# Solenoid_Boardv2.net
KiCad netlist of a schematic drawn in EAGLE
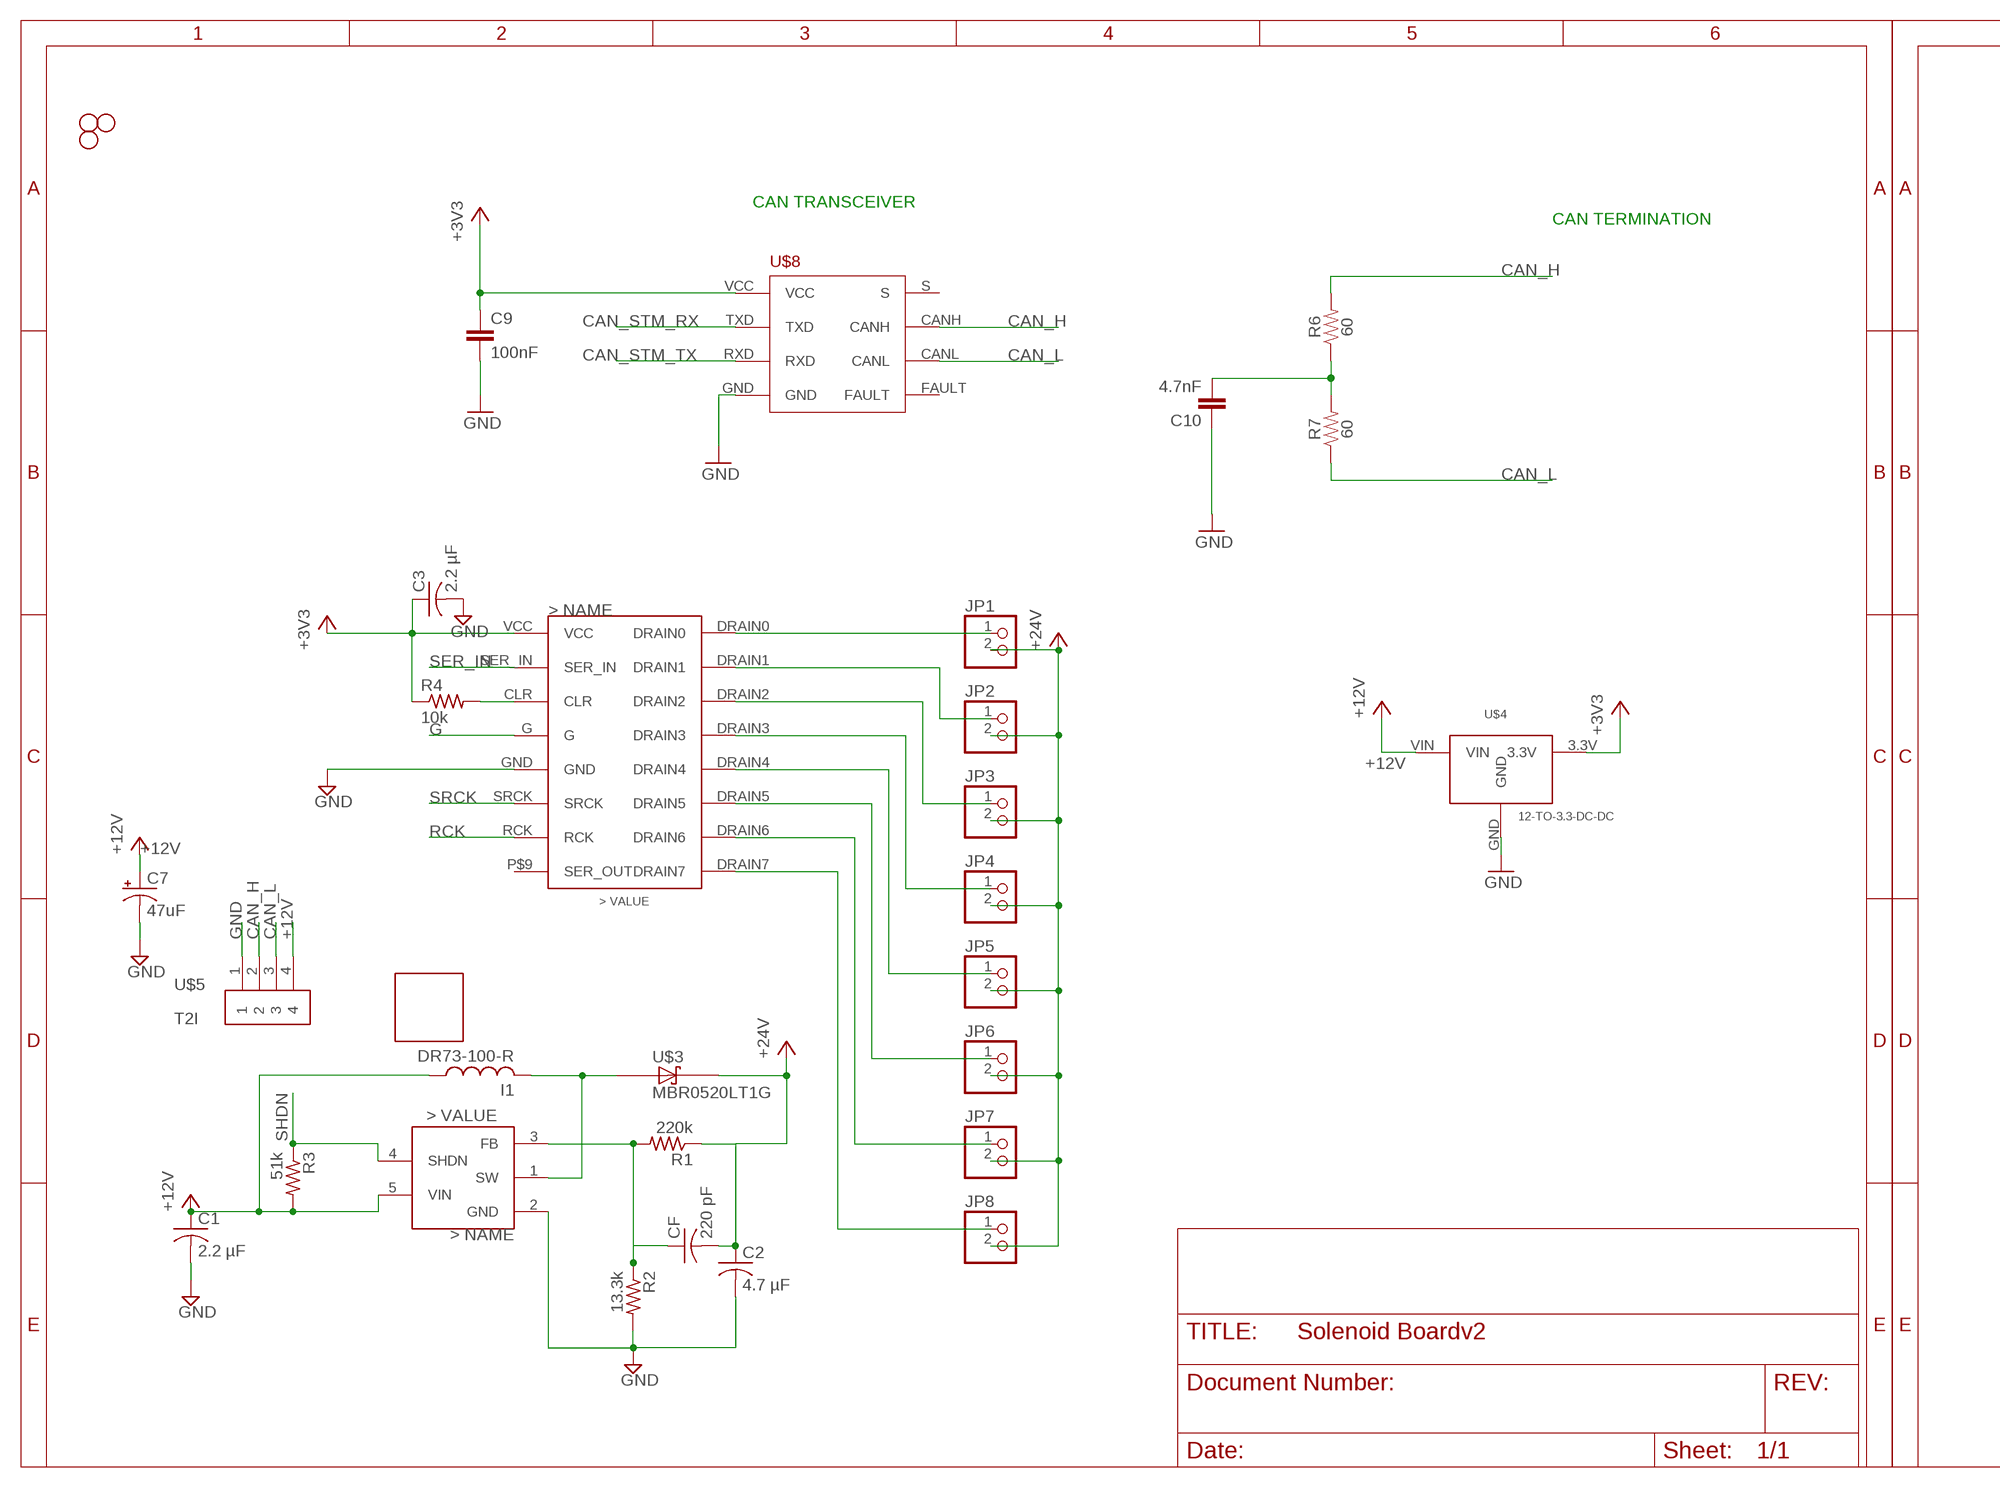
[diagram p0: schematic, sheet 1, part 1 of 2]
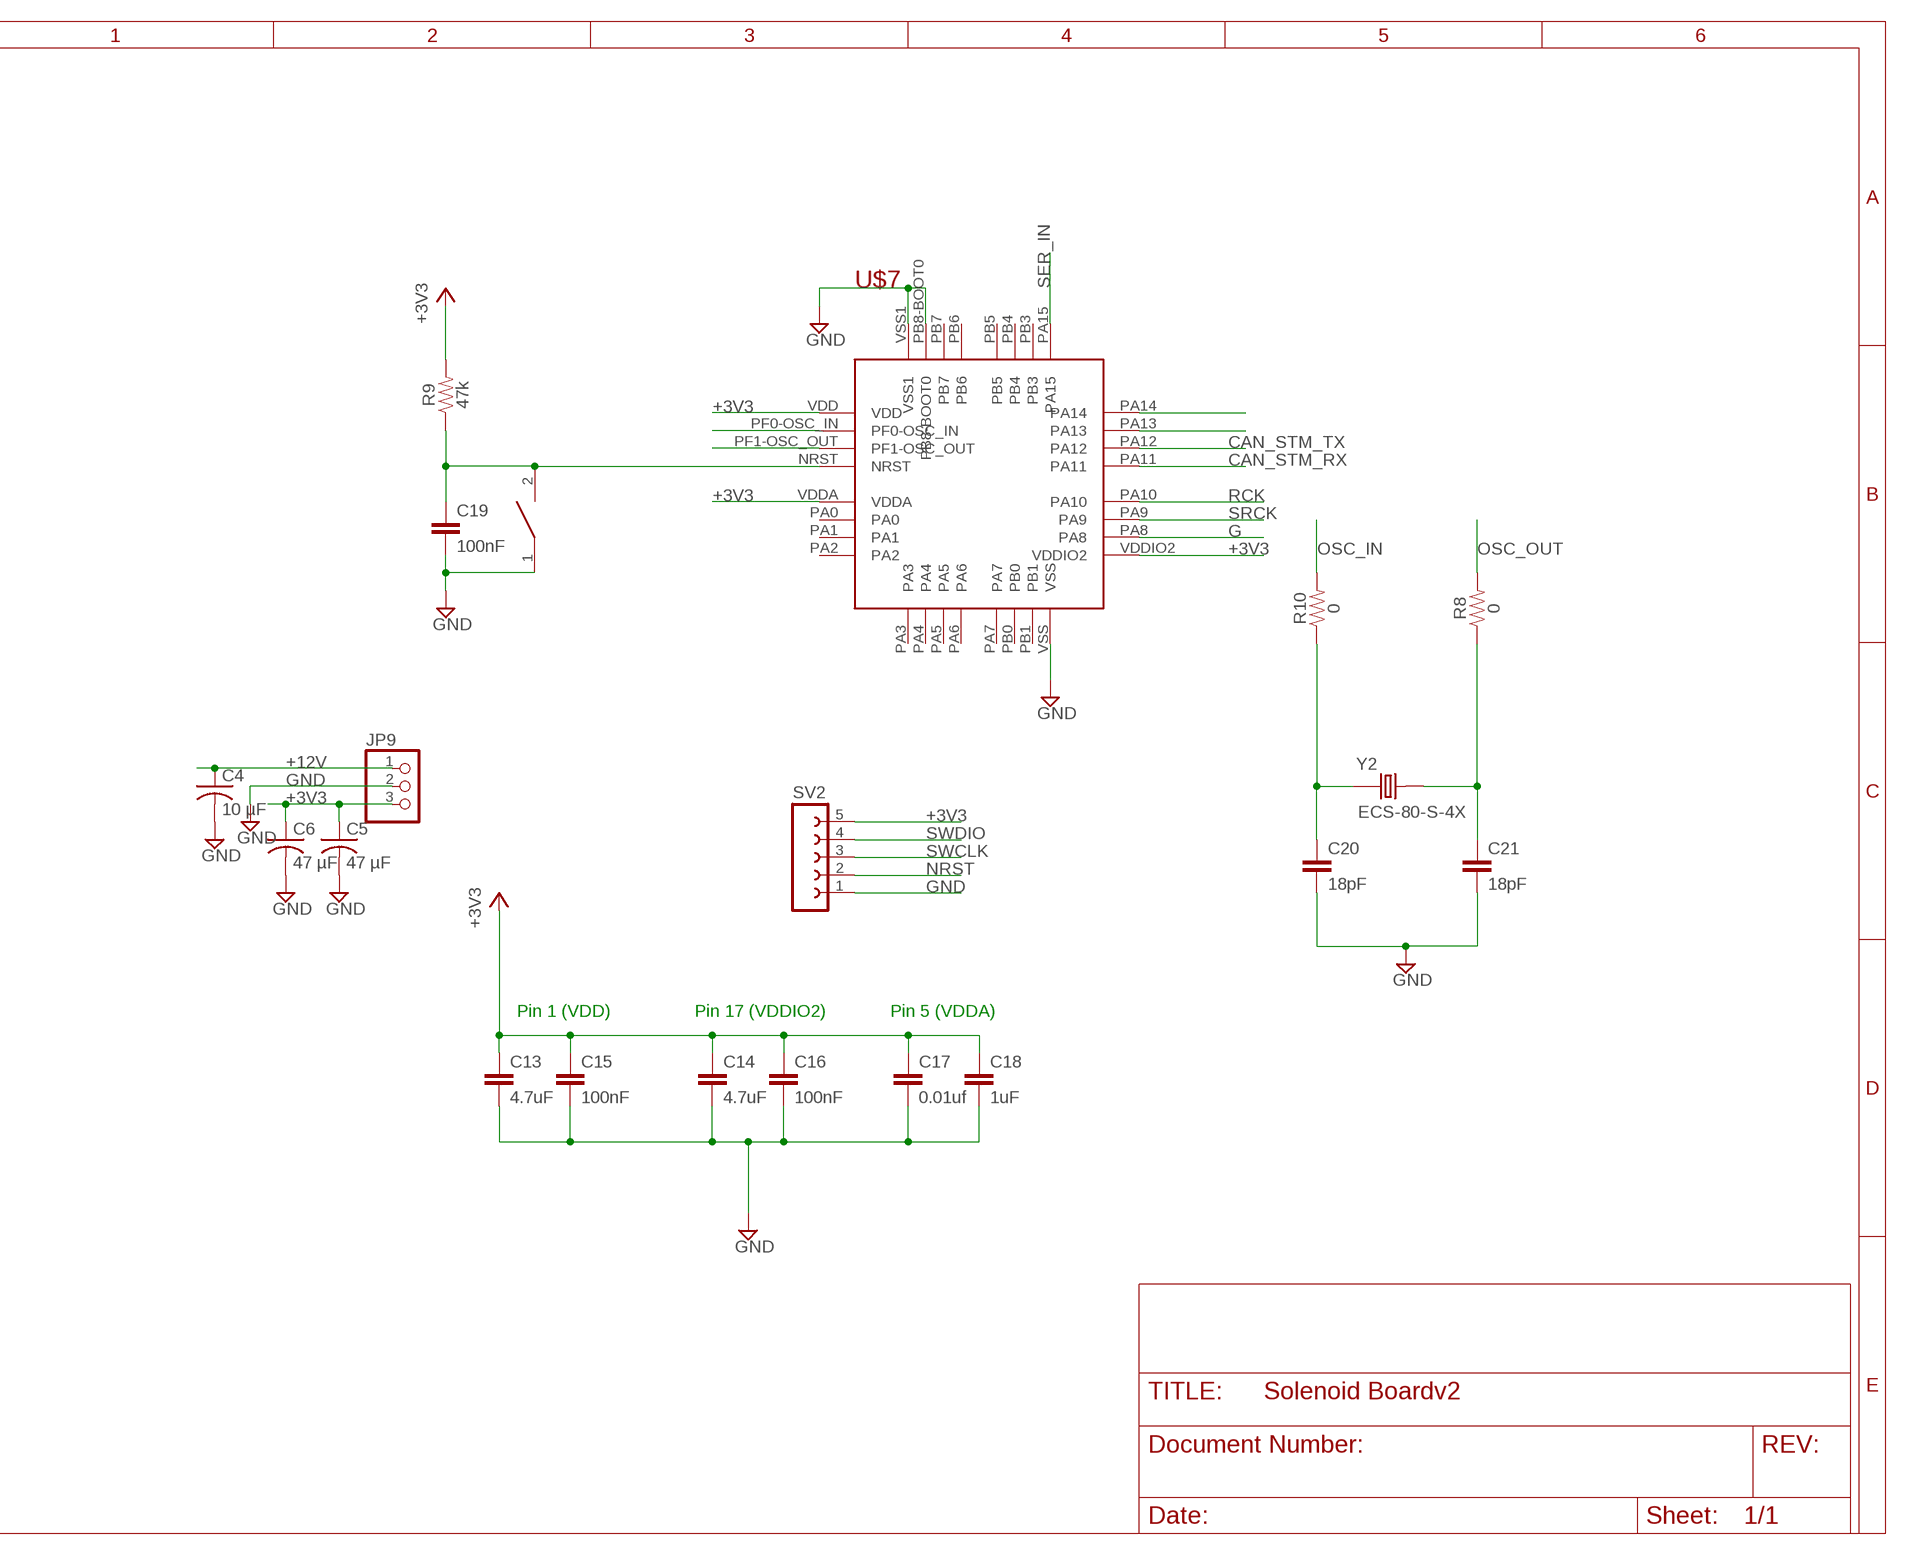
[diagram p1: schematic, sheet 1, part 2 of 2]

(export (version "E")
  (design (tool "Eeschema 10.0.6"))
  (components
    (comp (ref "C1")
      (value "2.2 µF")
      (footprint "eagle-import:C0805")
      (libsource (lib "eagle-import") (part "C-USC0805"))
    )
    (comp (ref "C2")
      (value "4.7 µF")
      (footprint "eagle-import:C0805")
      (libsource (lib "eagle-import") (part "C-USC0805"))
    )
    (comp (ref "C3")
      (value "2.2 µF")
      (footprint "eagle-import:C0805")
      (libsource (lib "eagle-import") (part "C-USC0805"))
    )
    (comp (ref "C4")
      (value "10 µF")
      (footprint "eagle-import:C0805")
      (libsource (lib "eagle-import") (part "C-USC0805"))
    )
    (comp (ref "C5")
      (value "47 µF")
      (footprint "eagle-import:C0805")
      (libsource (lib "eagle-import") (part "C-USC0805"))
    )
    (comp (ref "C6")
      (value "47 µF")
      (footprint "eagle-import:C0805")
      (libsource (lib "eagle-import") (part "C-USC0805"))
    )
    (comp (ref "C7")
      (value "47uF")
      (footprint "eagle-import:PANASONIC_D")
      (libsource (lib "eagle-import") (part "47UF-POLAR-PANASONIC_D-35V-20%"))
    )
    (comp (ref "C9")
      (value "100nF")
      (footprint "eagle-import:0603")
      (libsource (lib "eagle-import") (part "4.7UF0603"))
    )
    (comp (ref "C10")
      (value "4.7nF")
      (footprint "eagle-import:0603")
      (libsource (lib "eagle-import") (part "0.1UF-0603-25V-(+80/-20%)"))
    )
    (comp (ref "C13")
      (value "4.7uF")
      (footprint "eagle-import:0603")
      (libsource (lib "eagle-import") (part "4.7UF0603"))
    )
    (comp (ref "C14")
      (value "4.7uF")
      (footprint "eagle-import:0603")
      (libsource (lib "eagle-import") (part "4.7UF0603"))
    )
    (comp (ref "C15")
      (value "100nF")
      (footprint "eagle-import:0603")
      (libsource (lib "eagle-import") (part "4.7UF0603"))
    )
    (comp (ref "C16")
      (value "100nF")
      (footprint "eagle-import:0603")
      (libsource (lib "eagle-import") (part "4.7UF0603"))
    )
    (comp (ref "C17")
      (value "0.01uf")
      (footprint "eagle-import:0603")
      (libsource (lib "eagle-import") (part "4.7UF0603"))
    )
    (comp (ref "C18")
      (value "1uF")
      (footprint "eagle-import:0603")
      (libsource (lib "eagle-import") (part "4.7UF0603"))
    )
    (comp (ref "C19")
      (value "100nF")
      (footprint "eagle-import:0603")
      (libsource (lib "eagle-import") (part "4.7UF0603"))
    )
    (comp (ref "C20")
      (value "18pF")
      (footprint "eagle-import:0603")
      (libsource (lib "eagle-import") (part "4.7UF0603"))
    )
    (comp (ref "C21")
      (value "18pF")
      (footprint "eagle-import:0603")
      (libsource (lib "eagle-import") (part "4.7UF0603"))
    )
    (comp (ref "CF")
      (value "220 pF")
      (footprint "eagle-import:C0805")
      (libsource (lib "eagle-import") (part "C-USC0805"))
    )
    (comp (ref "H1")
      (value "STAND-OFF")
      (footprint "eagle-import:STAND-OFF")
      (libsource (lib "eagle-import") (part "STAND-OFF"))
    )
    (comp (ref "H2")
      (value "STAND-OFF")
      (footprint "eagle-import:STAND-OFF")
      (libsource (lib "eagle-import") (part "STAND-OFF"))
    )
    (comp (ref "H3")
      (value "STAND-OFF")
      (footprint "eagle-import:STAND-OFF")
      (libsource (lib "eagle-import") (part "STAND-OFF"))
    )
    (comp (ref "I1")
      (value "DR73-100-R")
      (footprint "eagle-import:DR73-100-R")
      (libsource (lib "eagle-import") (part "DR73-100-R"))
    )
    (comp (ref "JP1")
      (value "PINHD-1X2")
      (footprint "eagle-import:1X02")
      (libsource (lib "eagle-import") (part "PINHD-1X2"))
    )
    (comp (ref "JP2")
      (value "PINHD-1X2")
      (footprint "eagle-import:1X02")
      (libsource (lib "eagle-import") (part "PINHD-1X2"))
    )
    (comp (ref "JP3")
      (value "PINHD-1X2")
      (footprint "eagle-import:1X02")
      (libsource (lib "eagle-import") (part "PINHD-1X2"))
    )
    (comp (ref "JP4")
      (value "PINHD-1X2")
      (footprint "eagle-import:1X02")
      (libsource (lib "eagle-import") (part "PINHD-1X2"))
    )
    (comp (ref "JP5")
      (value "PINHD-1X2")
      (footprint "eagle-import:1X02")
      (libsource (lib "eagle-import") (part "PINHD-1X2"))
    )
    (comp (ref "JP6")
      (value "PINHD-1X2")
      (footprint "eagle-import:1X02")
      (libsource (lib "eagle-import") (part "PINHD-1X2"))
    )
    (comp (ref "JP7")
      (value "PINHD-1X2")
      (footprint "eagle-import:1X02")
      (libsource (lib "eagle-import") (part "PINHD-1X2"))
    )
    (comp (ref "JP8")
      (value "PINHD-1X2")
      (footprint "eagle-import:1X02")
      (libsource (lib "eagle-import") (part "PINHD-1X2"))
    )
    (comp (ref "JP9")
      (value "PINHD-1X3")
      (footprint "eagle-import:1X03")
      (libsource (lib "eagle-import") (part "PINHD-1X3"))
    )
    (comp (ref "R1")
      (value "220k")
      (footprint "eagle-import:R0603")
      (libsource (lib "eagle-import") (part "R-US_R0603"))
    )
    (comp (ref "R2")
      (value "13.3k")
      (footprint "eagle-import:R0603")
      (libsource (lib "eagle-import") (part "R-US_R0603"))
    )
    (comp (ref "R3")
      (value "51k")
      (footprint "eagle-import:R0603")
      (libsource (lib "eagle-import") (part "R-US_R0603"))
    )
    (comp (ref "R4")
      (value "10k")
      (footprint "eagle-import:R0603")
      (libsource (lib "eagle-import") (part "R-US_R0603"))
    )
    (comp (ref "R6")
      (value "60")
      (footprint "eagle-import:0603")
      (libsource (lib "eagle-import") (part "1KOHM-0603-1/10W-1%"))
    )
    (comp (ref "R7")
      (value "60")
      (footprint "eagle-import:0603")
      (libsource (lib "eagle-import") (part "1KOHM-0603-1/10W-1%"))
    )
    (comp (ref "R8")
      (value "0")
      (footprint "eagle-import:0603")
      (libsource (lib "eagle-import") (part "1KOHM-0603-1/10W-1%"))
    )
    (comp (ref "R9")
      (value "47k")
      (footprint "eagle-import:0603")
      (libsource (lib "eagle-import") (part "1KOHM-0603-1/10W-1%"))
    )
    (comp (ref "R10")
      (value "0")
      (footprint "eagle-import:0603")
      (libsource (lib "eagle-import") (part "1KOHM-0603-1/10W-1%"))
    )
    (comp (ref "RESET1")
      (value "SWITCH")
      (footprint "eagle-import:SW_2512")
      (libsource (lib "eagle-import") (part "SWITCH"))
    )
    (comp (ref "SV2")
      (value "FE05-1")
      (footprint "eagle-import:FE05-1")
      (libsource (lib "eagle-import") (part "FE05-1"))
    )
    (comp (ref "U$1")
      (value "SHIFT_REGISTER")
      (footprint "eagle-import:SHIFT_REGISTER")
      (libsource (lib "eagle-import") (part "SHIFT_REGISTER"))
    )
    (comp (ref "U$2")
      (value "LM27313")
      (footprint "eagle-import:SOT95P300X145-5")
      (libsource (lib "eagle-import") (part "LM27313"))
    )
    (comp (ref "U$3")
      (value "MBR0520LT1G")
      (footprint "eagle-import:SOD3716X135")
      (libsource (lib "eagle-import") (part "MBR0520LT1G"))
    )
    (comp (ref "U$4")
      (value "12-TO-3.3-DC-DC")
      (footprint "eagle-import:MURATA-DCDC")
      (libsource (lib "eagle-import") (part "12-TO-3.3-DC-DC"))
    )
    (comp (ref "U$5")
      (value "T2I")
      (footprint "eagle-import:T2I")
      (libsource (lib "eagle-import") (part "T2I"))
    )
    (comp (ref "U$6")
      (value "BOARDPNE")
      (footprint "eagle-import:PNE")
      (libsource (lib "eagle-import") (part "BOARDPNE"))
    )
    (comp (ref "U$7")
      (value "STM32F042K6T6")
      (footprint "eagle-import:STM32F042K6T6")
      (libsource (lib "eagle-import") (part "STM32F042K6T6"))
    )
    (comp (ref "U$8")
      (value "TCAN337D")
      (footprint "eagle-import:TCAN337D")
      (libsource (lib "eagle-import") (part "TCAN337D"))
    )
    (comp (ref "Y2")
      (value "ECS-80-S-4X")
      (footprint "eagle-import:XTAL_ECS-80-S-4X")
      (fields (field (name "DIGI-KEY_PART_NUMBER") "X1057-ND") (field (name "MF") "ECS International"))
      (libsource (lib "eagle-import") (part "ECS-80-S-4X"))
    )
  )
  (nets
    (net (code "1") (name "+3V3") (class "Default")
      (node (ref "C13") (pin "1") (pinfunction "1_1") (pintype "passive"))
      (node (ref "C14") (pin "1") (pinfunction "1_1") (pintype "passive"))
      (node (ref "C15") (pin "1") (pinfunction "1_1") (pintype "passive"))
      (node (ref "C16") (pin "1") (pinfunction "1_1") (pintype "passive"))
      (node (ref "C17") (pin "1") (pinfunction "1_1") (pintype "passive"))
      (node (ref "C18") (pin "1") (pinfunction "1_1") (pintype "passive"))
      (node (ref "C3") (pin "1") (pinfunction "1_1") (pintype "passive"))
      (node (ref "C5") (pin "1") (pinfunction "1_1") (pintype "passive"))
      (node (ref "C6") (pin "1") (pinfunction "1_1") (pintype "passive"))
      (node (ref "C9") (pin "1") (pinfunction "1_1") (pintype "passive"))
      (node (ref "JP9") (pin "3") (pinfunction "3_3") (pintype "passive"))
      (node (ref "R4") (pin "1") (pinfunction "1_1") (pintype "passive"))
      (node (ref "R9") (pin "2") (pinfunction "2_2") (pintype "passive"))
      (node (ref "SV2") (pin "5") (pinfunction "5_5") (pintype "passive"))
      (node (ref "U$1") (pin "VCC") (pinfunction "VCC_VCC") (pintype "bidirectional"))
      (node (ref "U$4") (pin "3.3V") (pinfunction "3.3V_3.3V") (pintype "bidirectional"))
      (node (ref "U$7") (pin "VDD") (pinfunction "VDD_VDD") (pintype "bidirectional"))
      (node (ref "U$7") (pin "VDDA") (pinfunction "VDDA_VDDA") (pintype "bidirectional"))
      (node (ref "U$7") (pin "VDDIO2") (pinfunction "VDDIO2_VDDIO2") (pintype "bidirectional"))
      (node (ref "U$8") (pin "VCC") (pinfunction "VCC_VCC") (pintype "bidirectional"))
    )
    (net (code "2") (name "+12V") (class "Default")
      (node (ref "C1") (pin "1") (pinfunction "1_1") (pintype "passive"))
      (node (ref "C4") (pin "1") (pinfunction "1_1") (pintype "passive"))
      (node (ref "C7") (pin "+") (pinfunction "+_+") (pintype "passive"))
      (node (ref "I1") (pin "1") (pinfunction "1_1") (pintype "passive"))
      (node (ref "JP9") (pin "1") (pinfunction "1_1") (pintype "passive"))
      (node (ref "R3") (pin "2") (pinfunction "2_2") (pintype "passive"))
      (node (ref "U$2") (pin "5") (pinfunction "VIN_5") (pintype "bidirectional"))
      (node (ref "U$4") (pin "VIN") (pinfunction "VIN_VIN") (pintype "bidirectional"))
      (node (ref "U$5") (pin "4") (pinfunction "4_4") (pintype "bidirectional"))
    )
    (net (code "3") (name "+24V") (class "Default")
      (node (ref "C2") (pin "1") (pinfunction "1_1") (pintype "passive"))
      (node (ref "CF") (pin "2") (pinfunction "2_2") (pintype "passive"))
      (node (ref "JP1") (pin "2") (pinfunction "2_2") (pintype "passive"))
      (node (ref "JP2") (pin "2") (pinfunction "2_2") (pintype "passive"))
      (node (ref "JP3") (pin "2") (pinfunction "2_2") (pintype "passive"))
      (node (ref "JP4") (pin "2") (pinfunction "2_2") (pintype "passive"))
      (node (ref "JP5") (pin "2") (pinfunction "2_2") (pintype "passive"))
      (node (ref "JP6") (pin "2") (pinfunction "2_2") (pintype "passive"))
      (node (ref "JP7") (pin "2") (pinfunction "2_2") (pintype "passive"))
      (node (ref "JP8") (pin "2") (pinfunction "2_2") (pintype "passive"))
      (node (ref "R1") (pin "1") (pinfunction "1_1") (pintype "passive"))
      (node (ref "U$3") (pin "2") (pinfunction "C_2") (pintype "passive"))
    )
    (net (code "4") (name "/CAN_H") (class "Default")
      (node (ref "R6") (pin "2") (pinfunction "2_2") (pintype "passive"))
      (node (ref "U$5") (pin "2") (pinfunction "2_2") (pintype "bidirectional"))
      (node (ref "U$8") (pin "CANH") (pinfunction "CANH_CANH") (pintype "bidirectional"))
    )
    (net (code "5") (name "/CAN_L") (class "Default")
      (node (ref "R7") (pin "1") (pinfunction "1_1") (pintype "passive"))
      (node (ref "U$5") (pin "3") (pinfunction "3_3") (pintype "bidirectional"))
      (node (ref "U$8") (pin "CANL") (pinfunction "CANL_CANL") (pintype "bidirectional"))
    )
    (net (code "6") (name "/CAN_STM_RX") (class "Default")
      (node (ref "U$7") (pin "PA11") (pinfunction "PA11_PA11") (pintype "bidirectional"))
      (node (ref "U$8") (pin "TXD") (pinfunction "TXD_TXD") (pintype "bidirectional"))
    )
    (net (code "7") (name "/CAN_STM_TX") (class "Default")
      (node (ref "U$7") (pin "PA12") (pinfunction "PA12_PA12") (pintype "bidirectional"))
      (node (ref "U$8") (pin "RXD") (pinfunction "RXD_RXD") (pintype "bidirectional"))
    )
    (net (code "8") (name "/G") (class "Default")
      (node (ref "U$1") (pin "G") (pinfunction "G_G") (pintype "bidirectional"))
      (node (ref "U$7") (pin "PA8") (pinfunction "PA8_PA8") (pintype "bidirectional"))
    )
    (net (code "9") (name "/NRST") (class "Default")
      (node (ref "C19") (pin "1") (pinfunction "1_1") (pintype "passive"))
      (node (ref "R9") (pin "1") (pinfunction "1_1") (pintype "passive"))
      (node (ref "RESET1") (pin "2") (pinfunction "P$2_2") (pintype "bidirectional"))
      (node (ref "SV2") (pin "2") (pinfunction "2_2") (pintype "passive"))
      (node (ref "U$7") (pin "NRST") (pinfunction "NRST_NRST") (pintype "bidirectional"))
    )
    (net (code "10") (name "/OSC_IN") (class "Default")
      (node (ref "R10") (pin "2") (pinfunction "2_2") (pintype "passive"))
      (node (ref "U$7") (pin "PF0-OSC_IN") (pinfunction "PF0-OSC_IN_PF0-OSC_IN") (pintype "bidirectional"))
    )
    (net (code "11") (name "/OSC_OUT") (class "Default")
      (node (ref "R8") (pin "2") (pinfunction "2_2") (pintype "passive"))
      (node (ref "U$7") (pin "PF1-OSC_OUT") (pinfunction "PF1-OSC_OUT_PF1-OSC_OUT") (pintype "bidirectional"))
    )
    (net (code "12") (name "/RCK") (class "Default")
      (node (ref "U$1") (pin "RCK") (pinfunction "RCK_RCK") (pintype "bidirectional"))
      (node (ref "U$7") (pin "PA10") (pinfunction "PA10_PA10") (pintype "bidirectional"))
    )
    (net (code "13") (name "/SER_IN") (class "Default")
      (node (ref "U$1") (pin "SER_IN") (pinfunction "SER_IN_SER_IN") (pintype "bidirectional"))
      (node (ref "U$7") (pin "PA15") (pinfunction "PA15_PA15") (pintype "bidirectional"))
    )
    (net (code "14") (name "/SHDN") (class "Default")
      (node (ref "R3") (pin "1") (pinfunction "1_1") (pintype "passive"))
      (node (ref "U$2") (pin "4") (pinfunction "SHDN_4") (pintype "bidirectional"))
    )
    (net (code "15") (name "/SRCK") (class "Default")
      (node (ref "U$1") (pin "SRCK") (pinfunction "SRCK_SRCK") (pintype "bidirectional"))
      (node (ref "U$7") (pin "PA9") (pinfunction "PA9_PA9") (pintype "bidirectional"))
    )
    (net (code "16") (name "/SWCLK") (class "Default")
      (node (ref "SV2") (pin "3") (pinfunction "3_3") (pintype "passive"))
      (node (ref "U$7") (pin "PA14") (pinfunction "PA14_PA14") (pintype "bidirectional"))
    )
    (net (code "17") (name "/SWDIO") (class "Default")
      (node (ref "SV2") (pin "4") (pinfunction "4_4") (pintype "passive"))
      (node (ref "U$7") (pin "PA13") (pinfunction "PA13_PA13") (pintype "bidirectional"))
    )
    (net (code "18") (name "GND") (class "Default")
      (node (ref "C1") (pin "2") (pinfunction "2_2") (pintype "passive"))
      (node (ref "C10") (pin "1") (pinfunction "1_1") (pintype "passive"))
      (node (ref "C13") (pin "2") (pinfunction "2_2") (pintype "passive"))
      (node (ref "C14") (pin "2") (pinfunction "2_2") (pintype "passive"))
      (node (ref "C15") (pin "2") (pinfunction "2_2") (pintype "passive"))
      (node (ref "C16") (pin "2") (pinfunction "2_2") (pintype "passive"))
      (node (ref "C17") (pin "2") (pinfunction "2_2") (pintype "passive"))
      (node (ref "C18") (pin "2") (pinfunction "2_2") (pintype "passive"))
      (node (ref "C19") (pin "2") (pinfunction "2_2") (pintype "passive"))
      (node (ref "C2") (pin "2") (pinfunction "2_2") (pintype "passive"))
      (node (ref "C20") (pin "2") (pinfunction "2_2") (pintype "passive"))
      (node (ref "C21") (pin "2") (pinfunction "2_2") (pintype "passive"))
      (node (ref "C3") (pin "2") (pinfunction "2_2") (pintype "passive"))
      (node (ref "C4") (pin "2") (pinfunction "2_2") (pintype "passive"))
      (node (ref "C5") (pin "2") (pinfunction "2_2") (pintype "passive"))
      (node (ref "C6") (pin "2") (pinfunction "2_2") (pintype "passive"))
      (node (ref "C7") (pin "-") (pinfunction "-_-") (pintype "passive"))
      (node (ref "C9") (pin "2") (pinfunction "2_2") (pintype "passive"))
      (node (ref "JP9") (pin "2") (pinfunction "2_2") (pintype "passive"))
      (node (ref "R2") (pin "2") (pinfunction "2_2") (pintype "passive"))
      (node (ref "RESET1") (pin "1") (pinfunction "P$1_1") (pintype "bidirectional"))
      (node (ref "SV2") (pin "1") (pinfunction "1_1") (pintype "passive"))
      (node (ref "U$1") (pin "GND") (pinfunction "GND_GND") (pintype "bidirectional"))
      (node (ref "U$2") (pin "2") (pinfunction "GND_2") (pintype "bidirectional"))
      (node (ref "U$4") (pin "GND") (pinfunction "GND_GND") (pintype "bidirectional"))
      (node (ref "U$5") (pin "1") (pinfunction "1_1") (pintype "bidirectional"))
      (node (ref "U$7") (pin "PB8-BOOT0") (pinfunction "PB8-BOOT0_PB8-BOOT0") (pintype "bidirectional"))
      (node (ref "U$7") (pin "VSS") (pinfunction "VSS_VSS") (pintype "bidirectional"))
      (node (ref "U$7") (pin "VSS1") (pinfunction "VSS1_VSS1") (pintype "bidirectional"))
      (node (ref "U$8") (pin "GND") (pinfunction "GND_GND") (pintype "bidirectional"))
    )
    (net (code "19") (name "Net-(C10-Pad2)") (class "Default")
      (node (ref "C10") (pin "2") (pinfunction "2_2") (pintype "passive"))
      (node (ref "R6") (pin "1") (pinfunction "1_1") (pintype "passive"))
      (node (ref "R7") (pin "2") (pinfunction "2_2") (pintype "passive"))
    )
    (net (code "20") (name "Net-(C20-Pad1)") (class "Default")
      (node (ref "C20") (pin "1") (pinfunction "1_1") (pintype "passive"))
      (node (ref "R10") (pin "1") (pinfunction "1_1") (pintype "passive"))
      (node (ref "Y2") (pin "1") (pinfunction "1_1") (pintype "passive"))
    )
    (net (code "21") (name "Net-(C21-Pad1)") (class "Default")
      (node (ref "C21") (pin "1") (pinfunction "1_1") (pintype "passive"))
      (node (ref "R8") (pin "1") (pinfunction "1_1") (pintype "passive"))
      (node (ref "Y2") (pin "2") (pinfunction "2_2") (pintype "passive"))
    )
    (net (code "22") (name "Net-(JP1-Pad1)") (class "Default")
      (node (ref "JP1") (pin "1") (pinfunction "1_1") (pintype "passive"))
      (node (ref "U$1") (pin "DRAIN0") (pinfunction "DRAIN0_DRAIN0") (pintype "bidirectional"))
    )
    (net (code "23") (name "Net-(JP2-Pad1)") (class "Default")
      (node (ref "JP2") (pin "1") (pinfunction "1_1") (pintype "passive"))
      (node (ref "U$1") (pin "DRAIN1") (pinfunction "DRAIN1_DRAIN1") (pintype "bidirectional"))
    )
    (net (code "24") (name "Net-(JP3-Pad1)") (class "Default")
      (node (ref "JP3") (pin "1") (pinfunction "1_1") (pintype "passive"))
      (node (ref "U$1") (pin "DRAIN2") (pinfunction "DRAIN2_DRAIN2") (pintype "bidirectional"))
    )
    (net (code "25") (name "Net-(JP4-Pad1)") (class "Default")
      (node (ref "JP4") (pin "1") (pinfunction "1_1") (pintype "passive"))
      (node (ref "U$1") (pin "DRAIN3") (pinfunction "DRAIN3_DRAIN3") (pintype "bidirectional"))
    )
    (net (code "26") (name "Net-(JP5-Pad1)") (class "Default")
      (node (ref "JP5") (pin "1") (pinfunction "1_1") (pintype "passive"))
      (node (ref "U$1") (pin "DRAIN4") (pinfunction "DRAIN4_DRAIN4") (pintype "bidirectional"))
    )
    (net (code "27") (name "Net-(JP6-Pad1)") (class "Default")
      (node (ref "JP6") (pin "1") (pinfunction "1_1") (pintype "passive"))
      (node (ref "U$1") (pin "DRAIN5") (pinfunction "DRAIN5_DRAIN5") (pintype "bidirectional"))
    )
    (net (code "28") (name "Net-(JP7-Pad1)") (class "Default")
      (node (ref "JP7") (pin "1") (pinfunction "1_1") (pintype "passive"))
      (node (ref "U$1") (pin "DRAIN6") (pinfunction "DRAIN6_DRAIN6") (pintype "bidirectional"))
    )
    (net (code "29") (name "Net-(JP8-Pad1)") (class "Default")
      (node (ref "JP8") (pin "1") (pinfunction "1_1") (pintype "passive"))
      (node (ref "U$1") (pin "DRAIN7") (pinfunction "DRAIN7_DRAIN7") (pintype "bidirectional"))
    )
    (net (code "30") (name "Net-(R4-Pad2)") (class "Default")
      (node (ref "R4") (pin "2") (pinfunction "2_2") (pintype "passive"))
      (node (ref "U$1") (pin "CLR") (pinfunction "CLR_CLR") (pintype "bidirectional"))
    )
    (net (code "31") (name "Net-(U$2-FB)") (class "Default")
      (node (ref "CF") (pin "1") (pinfunction "1_1") (pintype "passive"))
      (node (ref "R1") (pin "2") (pinfunction "2_2") (pintype "passive"))
      (node (ref "R2") (pin "1") (pinfunction "1_1") (pintype "passive"))
      (node (ref "U$2") (pin "3") (pinfunction "FB_3") (pintype "bidirectional"))
    )
    (net (code "32") (name "Net-(U$2-SW)") (class "Default")
      (node (ref "I1") (pin "2") (pinfunction "2_2") (pintype "passive"))
      (node (ref "U$2") (pin "1") (pinfunction "SW_1") (pintype "bidirectional"))
      (node (ref "U$3") (pin "1") (pinfunction "A_1") (pintype "passive"))
    )
    (net (code "33") (name "unconnected-(U$1-SER_OUT-PadP$9)") (class "Default")
      (node (ref "U$1") (pin "P$9") (pinfunction "SER_OUT_P$9") (pintype "bidirectional"))
    )
    (net (code "34") (name "unconnected-(U$7-PadPA0)") (class "Default")
      (node (ref "U$7") (pin "PA0") (pinfunction "PA0_PA0") (pintype "bidirectional"))
    )
    (net (code "35") (name "unconnected-(U$7-PadPA1)") (class "Default")
      (node (ref "U$7") (pin "PA1") (pinfunction "PA1_PA1") (pintype "bidirectional"))
    )
    (net (code "36") (name "unconnected-(U$7-PadPA2)") (class "Default")
      (node (ref "U$7") (pin "PA2") (pinfunction "PA2_PA2") (pintype "bidirectional"))
    )
    (net (code "37") (name "unconnected-(U$7-PadPA3)") (class "Default")
      (node (ref "U$7") (pin "PA3") (pinfunction "PA3_PA3") (pintype "bidirectional"))
    )
    (net (code "38") (name "unconnected-(U$7-PadPA4)") (class "Default")
      (node (ref "U$7") (pin "PA4") (pinfunction "PA4_PA4") (pintype "bidirectional"))
    )
    (net (code "39") (name "unconnected-(U$7-PadPA5)") (class "Default")
      (node (ref "U$7") (pin "PA5") (pinfunction "PA5_PA5") (pintype "bidirectional"))
    )
    (net (code "40") (name "unconnected-(U$7-PadPA6)") (class "Default")
      (node (ref "U$7") (pin "PA6") (pinfunction "PA6_PA6") (pintype "bidirectional"))
    )
    (net (code "41") (name "unconnected-(U$7-PadPA7)") (class "Default")
      (node (ref "U$7") (pin "PA7") (pinfunction "PA7_PA7") (pintype "bidirectional"))
    )
    (net (code "42") (name "unconnected-(U$7-PadPB0)") (class "Default")
      (node (ref "U$7") (pin "PB0") (pinfunction "PB0_PB0") (pintype "bidirectional"))
    )
    (net (code "43") (name "unconnected-(U$7-PadPB1)") (class "Default")
      (node (ref "U$7") (pin "PB1") (pinfunction "PB1_PB1") (pintype "bidirectional"))
    )
    (net (code "44") (name "unconnected-(U$7-PadPB3)") (class "Default")
      (node (ref "U$7") (pin "PB3") (pinfunction "PB3_PB3") (pintype "bidirectional"))
    )
    (net (code "45") (name "unconnected-(U$7-PadPB4)") (class "Default")
      (node (ref "U$7") (pin "PB4") (pinfunction "PB4_PB4") (pintype "bidirectional"))
    )
    (net (code "46") (name "unconnected-(U$7-PadPB5)") (class "Default")
      (node (ref "U$7") (pin "PB5") (pinfunction "PB5_PB5") (pintype "bidirectional"))
    )
    (net (code "47") (name "unconnected-(U$7-PadPB6)") (class "Default")
      (node (ref "U$7") (pin "PB6") (pinfunction "PB6_PB6") (pintype "bidirectional"))
    )
    (net (code "48") (name "unconnected-(U$7-PadPB7)") (class "Default")
      (node (ref "U$7") (pin "PB7") (pinfunction "PB7_PB7") (pintype "bidirectional"))
    )
    (net (code "49") (name "unconnected-(U$8-PadFAULT)") (class "Default")
      (node (ref "U$8") (pin "FAULT") (pinfunction "FAULT_FAULT") (pintype "bidirectional"))
    )
    (net (code "50") (name "unconnected-(U$8-PadS)") (class "Default")
      (node (ref "U$8") (pin "S") (pinfunction "S_S") (pintype "bidirectional"))
    )
  )
)
